# 09_USB_HDMI.net
KiCad netlist of a schematic drawn in Altium Designer
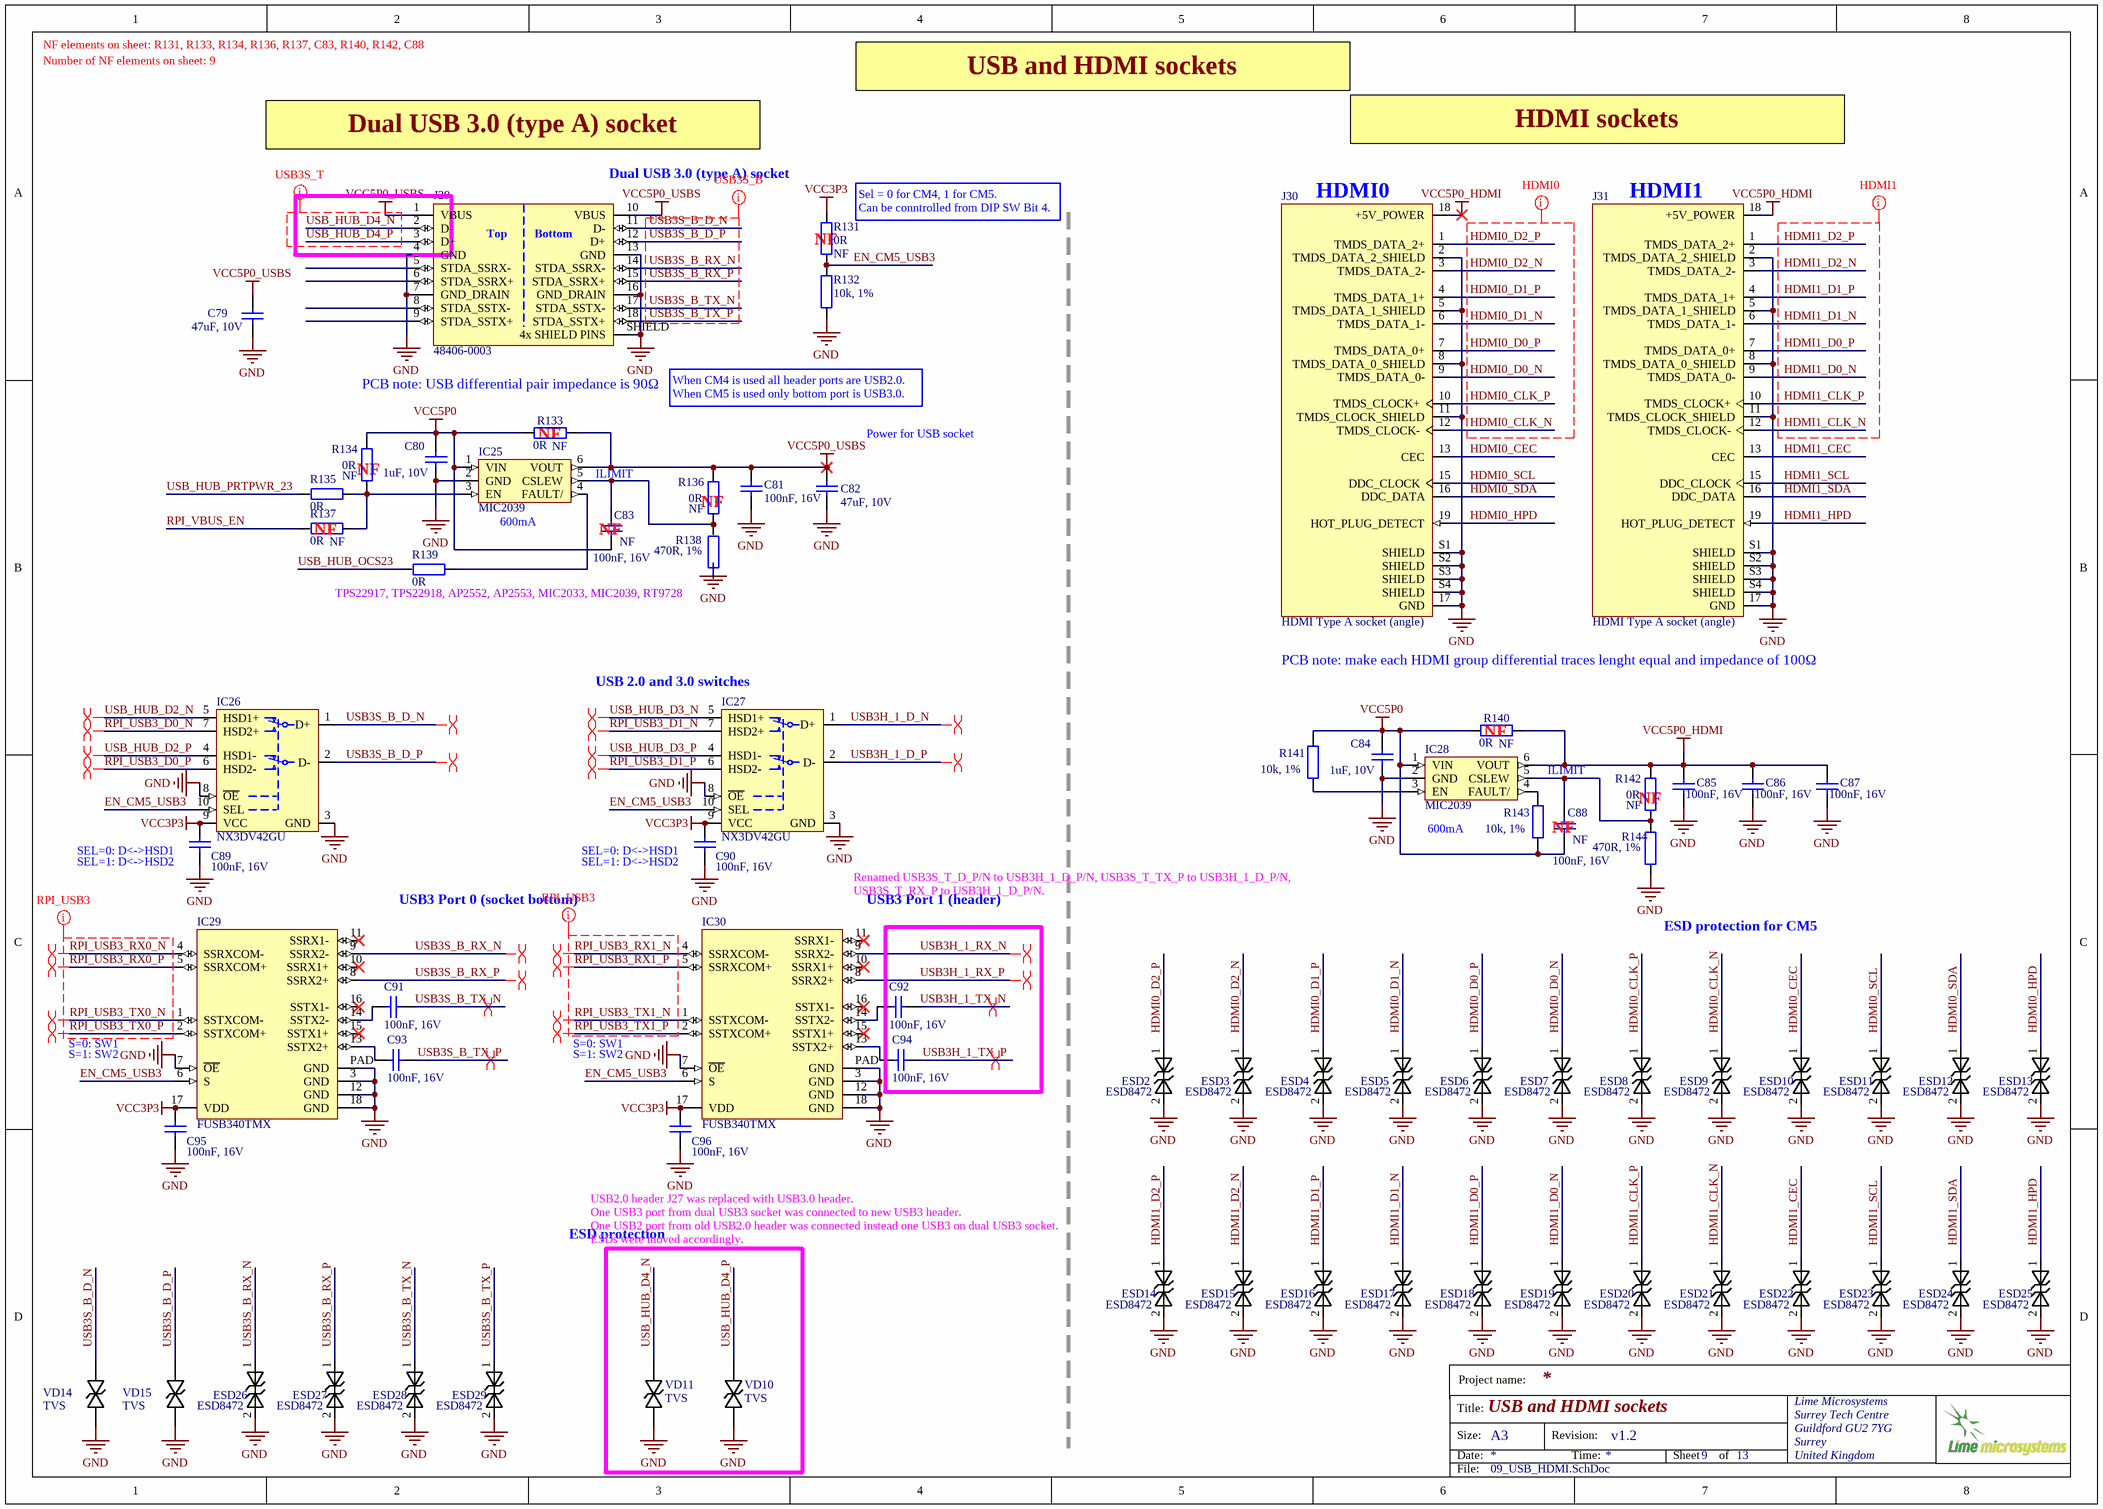
[diagram p0: 09_USB_HDMI.SchDoc]

(export (version "E")
  (design (tool "Eeschema 10.0.6"))
  (components
    (comp (ref "C79")
      (value "47uF, 10V")
      (footprint "CAP1206")
      (fields (field (name "TOLERANCE") "±20%") (field (name "MANUFACTURER") "TDK Corporation"))
      (libsource (lib "LimeFPGAboard_schLib") (part "Cap_1206"))
    )
    (comp (ref "C80")
      (value "1uF, 10V")
      (footprint "CAP0402")
      (fields (field (name "MANUFACTURER") "Yageo"))
      (libsource (lib "LimeMicroAltiumLib_schLib") (part "Cap_0402"))
    )
    (comp (ref "C81")
      (value "100nF, 16V")
      (footprint "CAP0402")
      (fields
        (field (name "MANUFACTURER") "Murata Electronics")
        (field (name "TOLERANCE") "10 %")
        (field (name "MANUFACTURER PART NUMBER") "GRM155R71C104KA88D")
      )
      (libsource (lib "LimeMicroAltiumLib_schLib") (part "Cap_0402"))
    )
    (comp (ref "C82")
      (value "47uF, 10V")
      (footprint "CAP1206")
      (fields (field (name "TOLERANCE") "±20%") (field (name "MANUFACTURER") "TDK Corporation"))
      (libsource (lib "LimeFPGAboard_schLib") (part "Cap_1206"))
    )
    (comp (ref "C83")
      (value "100nF, 16V")
      (footprint "CAP0402")
      (fields
        (field (name "ASSEMBLY INFO") "NF")
        (field (name "MANUFACTURER") "Murata Electronics")
        (field (name "TOLERANCE") "10 %")
        (field (name "MANUFACTURER PART NUMBER") "GRM155R71C104KA88D")
      )
      (libsource (lib "LimeMicroAltiumLib_schLib") (part "Cap_0402"))
    )
    (comp (ref "C84")
      (value "1uF, 10V")
      (footprint "CAP0402")
      (fields (field (name "MANUFACTURER") "Yageo"))
      (libsource (lib "LimeMicroAltiumLib_schLib") (part "Cap_0402"))
    )
    (comp (ref "C85")
      (value "100nF, 16V")
      (footprint "CAP0402")
      (fields
        (field (name "MANUFACTURER") "Murata Electronics")
        (field (name "TOLERANCE") "10 %")
        (field (name "MANUFACTURER PART NUMBER") "GRM155R71C104KA88D")
      )
      (libsource (lib "LimeMicroAltiumLib_schLib") (part "Cap_0402"))
    )
    (comp (ref "C86")
      (value "100nF, 16V")
      (footprint "CAP0402")
      (fields
        (field (name "MANUFACTURER") "Murata Electronics")
        (field (name "TOLERANCE") "10 %")
        (field (name "MANUFACTURER PART NUMBER") "GRM155R71C104KA88D")
      )
      (libsource (lib "LimeMicroAltiumLib_schLib") (part "Cap_0402"))
    )
    (comp (ref "C87")
      (value "100nF, 16V")
      (footprint "CAP0402")
      (fields
        (field (name "MANUFACTURER") "Murata Electronics")
        (field (name "TOLERANCE") "10 %")
        (field (name "MANUFACTURER PART NUMBER") "GRM155R71C104KA88D")
      )
      (libsource (lib "LimeMicroAltiumLib_schLib") (part "Cap_0402"))
    )
    (comp (ref "C88")
      (value "100nF, 16V")
      (footprint "CAP0402")
      (fields
        (field (name "ASSEMBLY INFO") "NF")
        (field (name "MANUFACTURER") "Murata Electronics")
        (field (name "TOLERANCE") "10 %")
        (field (name "MANUFACTURER PART NUMBER") "GRM155R71C104KA88D")
      )
      (libsource (lib "LimeMicroAltiumLib_schLib") (part "Cap_0402"))
    )
    (comp (ref "C89")
      (value "100nF, 16V")
      (footprint "CAP0402")
      (fields
        (field (name "MANUFACTURER") "Murata Electronics")
        (field (name "TOLERANCE") "10 %")
        (field (name "MANUFACTURER PART NUMBER") "GRM155R71C104KA88D")
      )
      (libsource (lib "") (part "Cap_0402_1"))
    )
    (comp (ref "C90")
      (value "100nF, 16V")
      (footprint "CAP0402")
      (fields
        (field (name "MANUFACTURER") "Murata Electronics")
        (field (name "TOLERANCE") "10 %")
        (field (name "MANUFACTURER PART NUMBER") "GRM155R71C104KA88D")
      )
      (libsource (lib "") (part "Cap_0402_1"))
    )
    (comp (ref "C91")
      (value "100nF, 16V")
      (footprint "CAP0402")
      (fields
        (field (name "MANUFACTURER") "Murata Electronics")
        (field (name "TOLERANCE") "10 %")
        (field (name "MANUFACTURER PART NUMBER") "GRM155R71C104KA88D")
      )
      (libsource (lib "") (part "Cap_0402_1"))
    )
    (comp (ref "C92")
      (value "100nF, 16V")
      (footprint "CAP0402")
      (fields
        (field (name "MANUFACTURER") "Murata Electronics")
        (field (name "TOLERANCE") "10 %")
        (field (name "MANUFACTURER PART NUMBER") "GRM155R71C104KA88D")
      )
      (libsource (lib "") (part "Cap_0402_1"))
    )
    (comp (ref "C93")
      (value "100nF, 16V")
      (footprint "CAP0402")
      (fields
        (field (name "MANUFACTURER") "Murata Electronics")
        (field (name "TOLERANCE") "10 %")
        (field (name "MANUFACTURER PART NUMBER") "GRM155R71C104KA88D")
      )
      (libsource (lib "") (part "Cap_0402_1"))
    )
    (comp (ref "C94")
      (value "100nF, 16V")
      (footprint "CAP0402")
      (fields
        (field (name "MANUFACTURER") "Murata Electronics")
        (field (name "TOLERANCE") "10 %")
        (field (name "MANUFACTURER PART NUMBER") "GRM155R71C104KA88D")
      )
      (libsource (lib "") (part "Cap_0402_1"))
    )
    (comp (ref "C95")
      (value "100nF, 16V")
      (footprint "CAP0402")
      (fields
        (field (name "MANUFACTURER") "Murata Electronics")
        (field (name "TOLERANCE") "10 %")
        (field (name "MANUFACTURER PART NUMBER") "GRM155R71C104KA88D")
      )
      (libsource (lib "") (part "Cap_0402_1"))
    )
    (comp (ref "C96")
      (value "100nF, 16V")
      (footprint "CAP0402")
      (fields
        (field (name "MANUFACTURER") "Murata Electronics")
        (field (name "TOLERANCE") "10 %")
        (field (name "MANUFACTURER PART NUMBER") "GRM155R71C104KA88D")
      )
      (libsource (lib "") (part "Cap_0402_1"))
    )
    (comp (ref "ESD2")
      (value "ESD8472")
      (footprint "ESD8472_X3DFN2")
      (fields (field (name "MANUFACTURER") "ON Semiconductor"))
      (libsource (lib "LimeMicroAltiumLib_schLib") (part "ESD8472"))
    )
    (comp (ref "ESD3")
      (value "ESD8472")
      (footprint "ESD8472_X3DFN2")
      (fields (field (name "MANUFACTURER") "ON Semiconductor"))
      (libsource (lib "LimeMicroAltiumLib_schLib") (part "ESD8472"))
    )
    (comp (ref "ESD4")
      (value "ESD8472")
      (footprint "ESD8472_X3DFN2")
      (fields (field (name "MANUFACTURER") "ON Semiconductor"))
      (libsource (lib "LimeMicroAltiumLib_schLib") (part "ESD8472"))
    )
    (comp (ref "ESD5")
      (value "ESD8472")
      (footprint "ESD8472_X3DFN2")
      (fields (field (name "MANUFACTURER") "ON Semiconductor"))
      (libsource (lib "LimeMicroAltiumLib_schLib") (part "ESD8472"))
    )
    (comp (ref "ESD6")
      (value "ESD8472")
      (footprint "ESD8472_X3DFN2")
      (fields (field (name "MANUFACTURER") "ON Semiconductor"))
      (libsource (lib "LimeMicroAltiumLib_schLib") (part "ESD8472"))
    )
    (comp (ref "ESD7")
      (value "ESD8472")
      (footprint "ESD8472_X3DFN2")
      (fields (field (name "MANUFACTURER") "ON Semiconductor"))
      (libsource (lib "LimeMicroAltiumLib_schLib") (part "ESD8472"))
    )
    (comp (ref "ESD8")
      (value "ESD8472")
      (footprint "ESD8472_X3DFN2")
      (fields (field (name "MANUFACTURER") "ON Semiconductor"))
      (libsource (lib "LimeMicroAltiumLib_schLib") (part "ESD8472"))
    )
    (comp (ref "ESD9")
      (value "ESD8472")
      (footprint "ESD8472_X3DFN2")
      (fields (field (name "MANUFACTURER") "ON Semiconductor"))
      (libsource (lib "LimeMicroAltiumLib_schLib") (part "ESD8472"))
    )
    (comp (ref "ESD10")
      (value "ESD8472")
      (footprint "ESD8472_X3DFN2")
      (fields (field (name "MANUFACTURER") "ON Semiconductor"))
      (libsource (lib "LimeMicroAltiumLib_schLib") (part "ESD8472"))
    )
    (comp (ref "ESD11")
      (value "ESD8472")
      (footprint "ESD8472_X3DFN2")
      (fields (field (name "MANUFACTURER") "ON Semiconductor"))
      (libsource (lib "LimeMicroAltiumLib_schLib") (part "ESD8472"))
    )
    (comp (ref "ESD12")
      (value "ESD8472")
      (footprint "ESD8472_X3DFN2")
      (fields (field (name "MANUFACTURER") "ON Semiconductor"))
      (libsource (lib "LimeMicroAltiumLib_schLib") (part "ESD8472"))
    )
    (comp (ref "ESD13")
      (value "ESD8472")
      (footprint "ESD8472_X3DFN2")
      (fields (field (name "MANUFACTURER") "ON Semiconductor"))
      (libsource (lib "LimeMicroAltiumLib_schLib") (part "ESD8472"))
    )
    (comp (ref "ESD14")
      (value "ESD8472")
      (footprint "ESD8472_X3DFN2")
      (fields (field (name "MANUFACTURER") "ON Semiconductor"))
      (libsource (lib "LimeMicroAltiumLib_schLib") (part "ESD8472"))
    )
    (comp (ref "ESD15")
      (value "ESD8472")
      (footprint "ESD8472_X3DFN2")
      (fields (field (name "MANUFACTURER") "ON Semiconductor"))
      (libsource (lib "LimeMicroAltiumLib_schLib") (part "ESD8472"))
    )
    (comp (ref "ESD16")
      (value "ESD8472")
      (footprint "ESD8472_X3DFN2")
      (fields (field (name "MANUFACTURER") "ON Semiconductor"))
      (libsource (lib "LimeMicroAltiumLib_schLib") (part "ESD8472"))
    )
    (comp (ref "ESD17")
      (value "ESD8472")
      (footprint "ESD8472_X3DFN2")
      (fields (field (name "MANUFACTURER") "ON Semiconductor"))
      (libsource (lib "LimeMicroAltiumLib_schLib") (part "ESD8472"))
    )
    (comp (ref "ESD18")
      (value "ESD8472")
      (footprint "ESD8472_X3DFN2")
      (fields (field (name "MANUFACTURER") "ON Semiconductor"))
      (libsource (lib "LimeMicroAltiumLib_schLib") (part "ESD8472"))
    )
    (comp (ref "ESD19")
      (value "ESD8472")
      (footprint "ESD8472_X3DFN2")
      (fields (field (name "MANUFACTURER") "ON Semiconductor"))
      (libsource (lib "LimeMicroAltiumLib_schLib") (part "ESD8472"))
    )
    (comp (ref "ESD20")
      (value "ESD8472")
      (footprint "ESD8472_X3DFN2")
      (fields (field (name "MANUFACTURER") "ON Semiconductor"))
      (libsource (lib "LimeMicroAltiumLib_schLib") (part "ESD8472"))
    )
    (comp (ref "ESD21")
      (value "ESD8472")
      (footprint "ESD8472_X3DFN2")
      (fields (field (name "MANUFACTURER") "ON Semiconductor"))
      (libsource (lib "LimeMicroAltiumLib_schLib") (part "ESD8472"))
    )
    (comp (ref "ESD22")
      (value "ESD8472")
      (footprint "ESD8472_X3DFN2")
      (fields (field (name "MANUFACTURER") "ON Semiconductor"))
      (libsource (lib "LimeMicroAltiumLib_schLib") (part "ESD8472"))
    )
    (comp (ref "ESD23")
      (value "ESD8472")
      (footprint "ESD8472_X3DFN2")
      (fields (field (name "MANUFACTURER") "ON Semiconductor"))
      (libsource (lib "LimeMicroAltiumLib_schLib") (part "ESD8472"))
    )
    (comp (ref "ESD24")
      (value "ESD8472")
      (footprint "ESD8472_X3DFN2")
      (fields (field (name "MANUFACTURER") "ON Semiconductor"))
      (libsource (lib "LimeMicroAltiumLib_schLib") (part "ESD8472"))
    )
    (comp (ref "ESD25")
      (value "ESD8472")
      (footprint "ESD8472_X3DFN2")
      (fields (field (name "MANUFACTURER") "ON Semiconductor"))
      (libsource (lib "LimeMicroAltiumLib_schLib") (part "ESD8472"))
    )
    (comp (ref "ESD26")
      (value "ESD8472")
      (footprint "ESD8472_X3DFN2")
      (fields (field (name "MANUFACTURER") "ON Semiconductor"))
      (libsource (lib "LimeMicroAltiumLib_schLib") (part "ESD8472"))
    )
    (comp (ref "ESD27")
      (value "ESD8472")
      (footprint "ESD8472_X3DFN2")
      (fields (field (name "MANUFACTURER") "ON Semiconductor"))
      (libsource (lib "LimeMicroAltiumLib_schLib") (part "ESD8472"))
    )
    (comp (ref "ESD28")
      (value "ESD8472")
      (footprint "ESD8472_X3DFN2")
      (fields (field (name "MANUFACTURER") "ON Semiconductor"))
      (libsource (lib "LimeMicroAltiumLib_schLib") (part "ESD8472"))
    )
    (comp (ref "ESD29")
      (value "ESD8472")
      (footprint "ESD8472_X3DFN2")
      (fields (field (name "MANUFACTURER") "ON Semiconductor"))
      (libsource (lib "LimeMicroAltiumLib_schLib") (part "ESD8472"))
    )
    (comp (ref "IC25")
      (value "MIC2039")
      (footprint "SOT23-6")
      (fields (field (name "MANUFACTURER") "Microchip"))
      (libsource (lib "LimeMicroAltiumLib_schLib_r04") (part "MIC2033_power_switch"))
    )
    (comp (ref "IC26")
      (value "NX3DV42GU")
      (footprint "FSUSB42UMX")
      (fields (field (name "MANUFACTURER") "NXP Semiconductors"))
      (libsource (lib "LimeMicroAltiumLib_schLib_r01") (part "FSUSB42UMX"))
    )
    (comp (ref "IC27")
      (value "NX3DV42GU")
      (footprint "FSUSB42UMX")
      (fields (field (name "MANUFACTURER") "NXP Semiconductors"))
      (libsource (lib "LimeMicroAltiumLib_schLib_r01") (part "FSUSB42UMX"))
    )
    (comp (ref "IC28")
      (value "MIC2039")
      (footprint "SOT23-6")
      (fields (field (name "MANUFACTURER") "Microchip"))
      (libsource (lib "LimeMicroAltiumLib_schLib_r04") (part "MIC2033_power_switch"))
    )
    (comp (ref "IC29")
      (value "FUSB340TMX")
      (footprint "FUSB340TMX_USB_switch_18-XFQFN")
      (fields (field (name "MANUFACTURER") "ON Semiconductor / Fairchild"))
      (libsource (lib "LimeMicroAltiumLib") (part "FUSB340TMX_USB_switch"))
    )
    (comp (ref "IC30")
      (value "FUSB340TMX")
      (footprint "FUSB340TMX_USB_switch_18-XFQFN")
      (fields (field (name "MANUFACTURER") "ON Semiconductor / Fairchild"))
      (libsource (lib "LimeMicroAltiumLib") (part "FUSB340TMX_USB_switch"))
    )
    (comp (ref "J29")
      (value "48406-0003")
      (footprint "Dual_USB_48406-0003_Molex")
      (fields (field (name "MANUFACTURER") "Molex"))
      (libsource (lib "LimeMicroAltiumLib") (part "Dual_USB_48406-0003_Molex"))
    )
    (comp (ref "J30")
      (value "HDMI Type A socket (angle)")
      (footprint "HDMI_HD01-19-RA-TH")
      (fields (field (name "MANUFACTURER") "CUI Devices"))
      (libsource (lib "LimeMicroAltiumLib_schLib_r04") (part "HDMI_HD01-19-RA-TH"))
    )
    (comp (ref "J31")
      (value "HDMI Type A socket (angle)")
      (footprint "HDMI_HD01-19-RA-TH")
      (fields (field (name "MANUFACTURER") "CUI Devices"))
      (libsource (lib "LimeMicroAltiumLib_schLib_r04") (part "HDMI_HD01-19-RA-TH"))
    )
    (comp (ref "R131")
      (value "0R")
      (footprint "RES0402")
      (fields
        (field (name "ASSEMBLY INFO") "NF")
        (field (name "MANUFACTURER") "Yageo")
        (field (name "TOLERANCE") "Jumper")
      )
      (libsource (lib "") (part "Res_0402_1"))
    )
    (comp (ref "R132")
      (value "10k, 1%")
      (footprint "RES0402")
      (fields (field (name "MANUFACTURER") "Yageo") (field (name "TOLERANCE") "±1%"))
      (libsource (lib "") (part "Res_0402_1"))
    )
    (comp (ref "R133")
      (value "0R")
      (footprint "RES0402")
      (fields
        (field (name "ASSEMBLY INFO") "NF")
        (field (name "MANUFACTURER") "Yageo")
        (field (name "TOLERANCE") "Jumper")
      )
      (libsource (lib "LimeMicroAltiumLib_schLib") (part "Res_0402"))
    )
    (comp (ref "R134")
      (value "0R")
      (footprint "RES0402")
      (fields
        (field (name "ASSEMBLY INFO") "NF")
        (field (name "MANUFACTURER") "Yageo")
        (field (name "TOLERANCE") "Jumper")
      )
      (libsource (lib "LimeMicroAltiumLib_schLib") (part "Res_0402"))
    )
    (comp (ref "R135")
      (value "0R")
      (footprint "RES0402")
      (fields (field (name "MANUFACTURER") "Yageo") (field (name "TOLERANCE") "Jumper"))
      (libsource (lib "LimeMicroAltiumLib_schLib") (part "Res_0402"))
    )
    (comp (ref "R136")
      (value "0R")
      (footprint "RES0402")
      (fields
        (field (name "ASSEMBLY INFO") "NF")
        (field (name "MANUFACTURER") "Yageo")
        (field (name "TOLERANCE") "Jumper")
      )
      (libsource (lib "LimeMicroAltiumLib_schLib") (part "Res_0402"))
    )
    (comp (ref "R137")
      (value "0R")
      (footprint "RES0402")
      (fields
        (field (name "ASSEMBLY INFO") "NF")
        (field (name "MANUFACTURER") "Yageo")
        (field (name "TOLERANCE") "Jumper")
      )
      (libsource (lib "LimeMicroAltiumLib_schLib") (part "Res_0402"))
    )
    (comp (ref "R138")
      (value "470R, 1%")
      (footprint "RES0402")
      (fields (field (name "TOLERANCE") "1%") (field (name "MANUFACTURER") "Yageo"))
      (libsource (lib "LimeMicroAltiumLib_schLib") (part "Res_0402"))
    )
    (comp (ref "R139")
      (value "0R")
      (footprint "RES0402")
      (fields (field (name "MANUFACTURER") "Yageo") (field (name "TOLERANCE") "Jumper"))
      (libsource (lib "LimeMicroAltiumLib_schLib") (part "Res_0402"))
    )
    (comp (ref "R140")
      (value "0R")
      (footprint "RES0402")
      (fields
        (field (name "ASSEMBLY INFO") "NF")
        (field (name "MANUFACTURER") "Yageo")
        (field (name "TOLERANCE") "Jumper")
      )
      (libsource (lib "LimeMicroAltiumLib_schLib") (part "Res_0402"))
    )
    (comp (ref "R141")
      (value "10k, 1%")
      (footprint "RES0402")
      (fields (field (name "MANUFACTURER") "Yageo") (field (name "TOLERANCE") "±1%"))
      (libsource (lib "") (part "Res_0402_1"))
    )
    (comp (ref "R142")
      (value "0R")
      (footprint "RES0402")
      (fields
        (field (name "ASSEMBLY INFO") "NF")
        (field (name "MANUFACTURER") "Yageo")
        (field (name "TOLERANCE") "Jumper")
      )
      (libsource (lib "LimeMicroAltiumLib_schLib") (part "Res_0402"))
    )
    (comp (ref "R143")
      (value "10k, 1%")
      (footprint "RES0402")
      (fields (field (name "MANUFACTURER") "Yageo") (field (name "TOLERANCE") "±1%"))
      (libsource (lib "") (part "Res_0402_1"))
    )
    (comp (ref "R144")
      (value "470R, 1%")
      (footprint "RES0402")
      (fields (field (name "TOLERANCE") "1%") (field (name "MANUFACTURER") "Yageo"))
      (libsource (lib "LimeMicroAltiumLib_schLib") (part "Res_0402"))
    )
    (comp (ref "VD10")
      (value "TVS")
      (footprint "SOD323")
      (fields
        (field (name "MANUFACTURER PART NUMBER") "SD03LCC")
        (field (name "MANUFACTURER") "Sangdest Microelectronics")
      )
      (libsource (lib "LimeNet-Micro_2v1-SDR") (part "DIODE_TVS"))
    )
    (comp (ref "VD11")
      (value "TVS")
      (footprint "SOD323")
      (fields
        (field (name "MANUFACTURER PART NUMBER") "SD03LCC")
        (field (name "MANUFACTURER") "Sangdest Microelectronics")
      )
      (libsource (lib "LimeNet-Micro_2v1-SDR") (part "DIODE_TVS"))
    )
    (comp (ref "VD14")
      (value "TVS")
      (footprint "SOD323")
      (fields
        (field (name "MANUFACTURER PART NUMBER") "SD03LCC")
        (field (name "MANUFACTURER") "Sangdest Microelectronics")
      )
      (libsource (lib "LimeNet-Micro_2v1-SDR") (part "DIODE_TVS"))
    )
    (comp (ref "VD15")
      (value "TVS")
      (footprint "SOD323")
      (fields
        (field (name "MANUFACTURER PART NUMBER") "SD03LCC")
        (field (name "MANUFACTURER") "Sangdest Microelectronics")
      )
      (libsource (lib "LimeNet-Micro_2v1-SDR") (part "DIODE_TVS"))
    )
  )
  (nets
    (net (code "1") (name "/EN_CM5_USB3") (class "Default")
      (node (ref "IC26") (pin "10") (pinfunction "SEL_10") (pintype "input"))
      (node (ref "IC27") (pin "10") (pinfunction "SEL_10") (pintype "input"))
      (node (ref "IC29") (pin "6") (pinfunction "S_6") (pintype "input"))
      (node (ref "IC30") (pin "6") (pinfunction "S_6") (pintype "input"))
      (node (ref "R131") (pin "1") (pinfunction "1_1") (pintype "passive"))
      (node (ref "R132") (pin "1") (pinfunction "1_1") (pintype "passive"))
    )
    (net (code "2") (name "/HDMI0_CEC") (class "Default")
      (node (ref "ESD10") (pin "1") (pinfunction "1_1") (pintype "passive"))
      (node (ref "J30") (pin "13") (pinfunction "CEC_13") (pintype "bidirectional"))
    )
    (net (code "3") (name "/HDMI0_CLK_N") (class "Default")
      (node (ref "ESD9") (pin "1") (pinfunction "1_1") (pintype "passive"))
      (node (ref "J30") (pin "12") (pinfunction "TMDS_CLOCK-_12") (pintype "bidirectional"))
    )
    (net (code "4") (name "/HDMI0_CLK_P") (class "Default")
      (node (ref "ESD8") (pin "1") (pinfunction "1_1") (pintype "passive"))
      (node (ref "J30") (pin "10") (pinfunction "TMDS_CLOCK+_10") (pintype "bidirectional"))
    )
    (net (code "5") (name "/HDMI0_D0_N") (class "Default")
      (node (ref "ESD7") (pin "1") (pinfunction "1_1") (pintype "passive"))
      (node (ref "J30") (pin "9") (pinfunction "TMDS_DATA_0-_9") (pintype "bidirectional"))
    )
    (net (code "6") (name "/HDMI0_D0_P") (class "Default")
      (node (ref "ESD6") (pin "1") (pinfunction "1_1") (pintype "passive"))
      (node (ref "J30") (pin "7") (pinfunction "TMDS_DATA_0+_7") (pintype "bidirectional"))
    )
    (net (code "7") (name "/HDMI0_D1_N") (class "Default")
      (node (ref "ESD5") (pin "1") (pinfunction "1_1") (pintype "passive"))
      (node (ref "J30") (pin "6") (pinfunction "TMDS_DATA_1-_6") (pintype "bidirectional"))
    )
    (net (code "8") (name "/HDMI0_D1_P") (class "Default")
      (node (ref "ESD4") (pin "1") (pinfunction "1_1") (pintype "passive"))
      (node (ref "J30") (pin "4") (pinfunction "TMDS_DATA_1+_4") (pintype "bidirectional"))
    )
    (net (code "9") (name "/HDMI0_D2_N") (class "Default")
      (node (ref "ESD3") (pin "1") (pinfunction "1_1") (pintype "passive"))
      (node (ref "J30") (pin "3") (pinfunction "TMDS_DATA_2-_3") (pintype "bidirectional"))
    )
    (net (code "10") (name "/HDMI0_D2_P") (class "Default")
      (node (ref "ESD2") (pin "1") (pinfunction "1_1") (pintype "passive"))
      (node (ref "J30") (pin "1") (pinfunction "TMDS_DATA_2+_1") (pintype "bidirectional"))
    )
    (net (code "11") (name "/HDMI0_HPD") (class "Default")
      (node (ref "ESD13") (pin "1") (pinfunction "1_1") (pintype "passive"))
      (node (ref "J30") (pin "19") (pinfunction "HOT_PLUG_DETECT_19") (pintype "input"))
    )
    (net (code "12") (name "/HDMI0_SCL") (class "Default")
      (node (ref "ESD11") (pin "1") (pinfunction "1_1") (pintype "passive"))
      (node (ref "J30") (pin "15") (pinfunction "DDC_CLOCK_15") (pintype "bidirectional"))
    )
    (net (code "13") (name "/HDMI0_SDA") (class "Default")
      (node (ref "ESD12") (pin "1") (pinfunction "1_1") (pintype "passive"))
      (node (ref "J30") (pin "16") (pinfunction "DDC_DATA_16") (pintype "bidirectional"))
    )
    (net (code "14") (name "/HDMI1_CEC") (class "Default")
      (node (ref "ESD22") (pin "1") (pinfunction "1_1") (pintype "passive"))
      (node (ref "J31") (pin "13") (pinfunction "CEC_13") (pintype "bidirectional"))
    )
    (net (code "15") (name "/HDMI1_CLK_N") (class "Default")
      (node (ref "ESD21") (pin "1") (pinfunction "1_1") (pintype "passive"))
      (node (ref "J31") (pin "12") (pinfunction "TMDS_CLOCK-_12") (pintype "bidirectional"))
    )
    (net (code "16") (name "/HDMI1_CLK_P") (class "Default")
      (node (ref "ESD20") (pin "1") (pinfunction "1_1") (pintype "passive"))
      (node (ref "J31") (pin "10") (pinfunction "TMDS_CLOCK+_10") (pintype "bidirectional"))
    )
    (net (code "17") (name "/HDMI1_D0_N") (class "Default")
      (node (ref "ESD19") (pin "1") (pinfunction "1_1") (pintype "passive"))
      (node (ref "J31") (pin "9") (pinfunction "TMDS_DATA_0-_9") (pintype "bidirectional"))
    )
    (net (code "18") (name "/HDMI1_D0_P") (class "Default")
      (node (ref "ESD18") (pin "1") (pinfunction "1_1") (pintype "passive"))
      (node (ref "J31") (pin "7") (pinfunction "TMDS_DATA_0+_7") (pintype "bidirectional"))
    )
    (net (code "19") (name "/HDMI1_D1_N") (class "Default")
      (node (ref "ESD17") (pin "1") (pinfunction "1_1") (pintype "passive"))
      (node (ref "J31") (pin "6") (pinfunction "TMDS_DATA_1-_6") (pintype "bidirectional"))
    )
    (net (code "20") (name "/HDMI1_D1_P") (class "Default")
      (node (ref "ESD16") (pin "1") (pinfunction "1_1") (pintype "passive"))
      (node (ref "J31") (pin "4") (pinfunction "TMDS_DATA_1+_4") (pintype "bidirectional"))
    )
    (net (code "21") (name "/HDMI1_D2_N") (class "Default")
      (node (ref "ESD15") (pin "1") (pinfunction "1_1") (pintype "passive"))
      (node (ref "J31") (pin "3") (pinfunction "TMDS_DATA_2-_3") (pintype "bidirectional"))
    )
    (net (code "22") (name "/HDMI1_D2_P") (class "Default")
      (node (ref "ESD14") (pin "1") (pinfunction "1_1") (pintype "passive"))
      (node (ref "J31") (pin "1") (pinfunction "TMDS_DATA_2+_1") (pintype "bidirectional"))
    )
    (net (code "23") (name "/HDMI1_HPD") (class "Default")
      (node (ref "ESD25") (pin "1") (pinfunction "1_1") (pintype "passive"))
      (node (ref "J31") (pin "19") (pinfunction "HOT_PLUG_DETECT_19") (pintype "input"))
    )
    (net (code "24") (name "/HDMI1_SCL") (class "Default")
      (node (ref "ESD23") (pin "1") (pinfunction "1_1") (pintype "passive"))
      (node (ref "J31") (pin "15") (pinfunction "DDC_CLOCK_15") (pintype "bidirectional"))
    )
    (net (code "25") (name "/HDMI1_SDA") (class "Default")
      (node (ref "ESD24") (pin "1") (pinfunction "1_1") (pintype "passive"))
      (node (ref "J31") (pin "16") (pinfunction "DDC_DATA_16") (pintype "bidirectional"))
    )
    (net (code "26") (name "/RPI_USB3_D0_N") (class "Default")
      (node (ref "IC26") (pin "7") (pinfunction "HSD2+_7") (pintype "passive"))
    )
    (net (code "27") (name "/RPI_USB3_D0_P") (class "Default")
      (node (ref "IC26") (pin "6") (pinfunction "HSD2-_6") (pintype "passive"))
    )
    (net (code "28") (name "/RPI_USB3_D1_N") (class "Default")
      (node (ref "IC27") (pin "7") (pinfunction "HSD2+_7") (pintype "passive"))
    )
    (net (code "29") (name "/RPI_USB3_D1_P") (class "Default")
      (node (ref "IC27") (pin "6") (pinfunction "HSD2-_6") (pintype "passive"))
    )
    (net (code "30") (name "/RPI_USB3_RX0_N") (class "Default")
      (node (ref "IC29") (pin "4") (pinfunction "SSRXCOM-_4") (pintype "bidirectional"))
    )
    (net (code "31") (name "/RPI_USB3_RX0_P") (class "Default")
      (node (ref "IC29") (pin "5") (pinfunction "SSRXCOM+_5") (pintype "bidirectional"))
    )
    (net (code "32") (name "/RPI_USB3_RX1_N") (class "Default")
      (node (ref "IC30") (pin "4") (pinfunction "SSRXCOM-_4") (pintype "bidirectional"))
    )
    (net (code "33") (name "/RPI_USB3_RX1_P") (class "Default")
      (node (ref "IC30") (pin "5") (pinfunction "SSRXCOM+_5") (pintype "bidirectional"))
    )
    (net (code "34") (name "/RPI_USB3_TX0_N") (class "Default")
      (node (ref "IC29") (pin "1") (pinfunction "SSTXCOM-_1") (pintype "bidirectional"))
    )
    (net (code "35") (name "/RPI_USB3_TX0_P") (class "Default")
      (node (ref "IC29") (pin "2") (pinfunction "SSTXCOM+_2") (pintype "bidirectional"))
    )
    (net (code "36") (name "/RPI_USB3_TX1_N") (class "Default")
      (node (ref "IC30") (pin "1") (pinfunction "SSTXCOM-_1") (pintype "bidirectional"))
    )
    (net (code "37") (name "/RPI_USB3_TX1_P") (class "Default")
      (node (ref "IC30") (pin "2") (pinfunction "SSTXCOM+_2") (pintype "bidirectional"))
    )
    (net (code "38") (name "/RPI_VBUS_EN") (class "Default")
      (node (ref "R137") (pin "2") (pinfunction "2_2") (pintype "passive"))
    )
    (net (code "39") (name "/USB3H_1_D_N") (class "Default")
      (node (ref "IC27") (pin "1") (pinfunction "D+_1") (pintype "passive"))
    )
    (net (code "40") (name "/USB3H_1_D_P") (class "Default")
      (node (ref "IC27") (pin "2") (pinfunction "D-_2") (pintype "passive"))
    )
    (net (code "41") (name "/USB3H_1_RX_N") (class "Default")
      (node (ref "IC30") (pin "9") (pinfunction "SSRX2-_9") (pintype "bidirectional"))
    )
    (net (code "42") (name "/USB3H_1_RX_P") (class "Default")
      (node (ref "IC30") (pin "8") (pinfunction "SSRX2+_8") (pintype "bidirectional"))
    )
    (net (code "43") (name "/USB3H_1_TX_N") (class "Default")
      (node (ref "C92") (pin "2") (pinfunction "2_2") (pintype "passive"))
    )
    (net (code "44") (name "/USB3H_1_TX_P") (class "Default")
      (node (ref "C94") (pin "2") (pinfunction "2_2") (pintype "passive"))
    )
    (net (code "45") (name "/USB3S_B_D_N") (class "Default")
      (node (ref "IC26") (pin "1") (pinfunction "D+_1") (pintype "passive"))
      (node (ref "J29") (pin "11") (pinfunction "D-_11") (pintype "bidirectional"))
      (node (ref "VD14") (pin "A") (pinfunction "A_A") (pintype "passive"))
    )
    (net (code "46") (name "/USB3S_B_D_P") (class "Default")
      (node (ref "IC26") (pin "2") (pinfunction "D-_2") (pintype "passive"))
      (node (ref "J29") (pin "12") (pinfunction "D+_12") (pintype "bidirectional"))
      (node (ref "VD15") (pin "A") (pinfunction "A_A") (pintype "passive"))
    )
    (net (code "47") (name "/USB3S_B_RX_N") (class "Default")
      (node (ref "ESD26") (pin "1") (pinfunction "1_1") (pintype "passive"))
      (node (ref "IC29") (pin "9") (pinfunction "SSRX2-_9") (pintype "bidirectional"))
      (node (ref "J29") (pin "14") (pinfunction "STDA_SSRX-_14") (pintype "bidirectional"))
    )
    (net (code "48") (name "/USB3S_B_RX_P") (class "Default")
      (node (ref "ESD27") (pin "1") (pinfunction "1_1") (pintype "passive"))
      (node (ref "IC29") (pin "8") (pinfunction "SSRX2+_8") (pintype "bidirectional"))
      (node (ref "J29") (pin "15") (pinfunction "STDA_SSRX+_15") (pintype "bidirectional"))
    )
    (net (code "49") (name "/USB3S_B_TX_N") (class "Default")
      (node (ref "C91") (pin "2") (pinfunction "2_2") (pintype "passive"))
      (node (ref "ESD28") (pin "1") (pinfunction "1_1") (pintype "passive"))
      (node (ref "J29") (pin "17") (pinfunction "STDA_SSTX-_17") (pintype "bidirectional"))
    )
    (net (code "50") (name "/USB3S_B_TX_P") (class "Default")
      (node (ref "C93") (pin "2") (pinfunction "2_2") (pintype "passive"))
      (node (ref "ESD29") (pin "1") (pinfunction "1_1") (pintype "passive"))
      (node (ref "J29") (pin "18") (pinfunction "STDA_SSTX+_18") (pintype "bidirectional"))
    )
    (net (code "51") (name "/USB_HUB_D2_N") (class "Default")
      (node (ref "IC26") (pin "5") (pinfunction "HSD1+_5") (pintype "passive"))
    )
    (net (code "52") (name "/USB_HUB_D2_P") (class "Default")
      (node (ref "IC26") (pin "4") (pinfunction "HSD1-_4") (pintype "passive"))
    )
    (net (code "53") (name "/USB_HUB_D3_N") (class "Default")
      (node (ref "IC27") (pin "5") (pinfunction "HSD1+_5") (pintype "passive"))
    )
    (net (code "54") (name "/USB_HUB_D3_P") (class "Default")
      (node (ref "IC27") (pin "4") (pinfunction "HSD1-_4") (pintype "passive"))
    )
    (net (code "55") (name "/USB_HUB_D4_N") (class "Default")
      (node (ref "J29") (pin "2") (pinfunction "D-_2") (pintype "bidirectional"))
      (node (ref "VD11") (pin "A") (pinfunction "A_A") (pintype "passive"))
    )
    (net (code "56") (name "/USB_HUB_D4_P") (class "Default")
      (node (ref "J29") (pin "3") (pinfunction "D+_3") (pintype "bidirectional"))
      (node (ref "VD10") (pin "A") (pinfunction "A_A") (pintype "passive"))
    )
    (net (code "57") (name "/USB_HUB_OCS23") (class "Default")
      (node (ref "R139") (pin "2") (pinfunction "2_2") (pintype "passive"))
    )
    (net (code "58") (name "/USB_HUB_PRTPWR_23") (class "Default")
      (node (ref "R135") (pin "2") (pinfunction "2_2") (pintype "passive"))
    )
    (net (code "59") (name "GND") (class "Default")
      (node (ref "C79") (pin "1") (pinfunction "1_1") (pintype "passive"))
      (node (ref "C80") (pin "2") (pinfunction "2_2") (pintype "passive"))
      (node (ref "C81") (pin "2") (pinfunction "2_2") (pintype "passive"))
      (node (ref "C82") (pin "1") (pinfunction "1_1") (pintype "passive"))
      (node (ref "C84") (pin "2") (pinfunction "2_2") (pintype "passive"))
      (node (ref "C85") (pin "2") (pinfunction "2_2") (pintype "passive"))
      (node (ref "C86") (pin "2") (pinfunction "2_2") (pintype "passive"))
      (node (ref "C87") (pin "2") (pinfunction "2_2") (pintype "passive"))
      (node (ref "C89") (pin "2") (pinfunction "2_2") (pintype "passive"))
      (node (ref "C90") (pin "2") (pinfunction "2_2") (pintype "passive"))
      (node (ref "C95") (pin "2") (pinfunction "2_2") (pintype "passive"))
      (node (ref "C96") (pin "2") (pinfunction "2_2") (pintype "passive"))
      (node (ref "ESD10") (pin "2") (pinfunction "2_2") (pintype "passive"))
      (node (ref "ESD11") (pin "2") (pinfunction "2_2") (pintype "passive"))
      (node (ref "ESD12") (pin "2") (pinfunction "2_2") (pintype "passive"))
      (node (ref "ESD13") (pin "2") (pinfunction "2_2") (pintype "passive"))
      (node (ref "ESD14") (pin "2") (pinfunction "2_2") (pintype "passive"))
      (node (ref "ESD15") (pin "2") (pinfunction "2_2") (pintype "passive"))
      (node (ref "ESD16") (pin "2") (pinfunction "2_2") (pintype "passive"))
      (node (ref "ESD17") (pin "2") (pinfunction "2_2") (pintype "passive"))
      (node (ref "ESD18") (pin "2") (pinfunction "2_2") (pintype "passive"))
      (node (ref "ESD19") (pin "2") (pinfunction "2_2") (pintype "passive"))
      (node (ref "ESD2") (pin "2") (pinfunction "2_2") (pintype "passive"))
      (node (ref "ESD20") (pin "2") (pinfunction "2_2") (pintype "passive"))
      (node (ref "ESD21") (pin "2") (pinfunction "2_2") (pintype "passive"))
      (node (ref "ESD22") (pin "2") (pinfunction "2_2") (pintype "passive"))
      (node (ref "ESD23") (pin "2") (pinfunction "2_2") (pintype "passive"))
      (node (ref "ESD24") (pin "2") (pinfunction "2_2") (pintype "passive"))
      (node (ref "ESD25") (pin "2") (pinfunction "2_2") (pintype "passive"))
      (node (ref "ESD26") (pin "2") (pinfunction "2_2") (pintype "passive"))
      (node (ref "ESD27") (pin "2") (pinfunction "2_2") (pintype "passive"))
      (node (ref "ESD28") (pin "2") (pinfunction "2_2") (pintype "passive"))
      (node (ref "ESD29") (pin "2") (pinfunction "2_2") (pintype "passive"))
      (node (ref "ESD3") (pin "2") (pinfunction "2_2") (pintype "passive"))
      (node (ref "ESD4") (pin "2") (pinfunction "2_2") (pintype "passive"))
      (node (ref "ESD5") (pin "2") (pinfunction "2_2") (pintype "passive"))
      (node (ref "ESD6") (pin "2") (pinfunction "2_2") (pintype "passive"))
      (node (ref "ESD7") (pin "2") (pinfunction "2_2") (pintype "passive"))
      (node (ref "ESD8") (pin "2") (pinfunction "2_2") (pintype "passive"))
      (node (ref "ESD9") (pin "2") (pinfunction "2_2") (pintype "passive"))
      (node (ref "IC25") (pin "2") (pinfunction "GND_2") (pintype "passive"))
      (node (ref "IC26") (pin "3") (pinfunction "GND_3") (pintype "passive"))
      (node (ref "IC26") (pin "8") (pinfunction "~{OE}_8") (pintype "input"))
      (node (ref "IC27") (pin "3") (pinfunction "GND_3") (pintype "passive"))
      (node (ref "IC27") (pin "8") (pinfunction "~{OE}_8") (pintype "input"))
      (node (ref "IC28") (pin "2") (pinfunction "GND_2") (pintype "passive"))
      (node (ref "IC29") (pin "12") (pinfunction "GND_12") (pintype "passive"))
      (node (ref "IC29") (pin "18") (pinfunction "GND_18") (pintype "passive"))
      (node (ref "IC29") (pin "3") (pinfunction "GND_3") (pintype "passive"))
      (node (ref "IC29") (pin "7") (pinfunction "~{OE}_7") (pintype "input"))
      (node (ref "IC29") (pin "PAD") (pinfunction "GND_PAD") (pintype "passive"))
      (node (ref "IC30") (pin "12") (pinfunction "GND_12") (pintype "passive"))
      (node (ref "IC30") (pin "18") (pinfunction "GND_18") (pintype "passive"))
      (node (ref "IC30") (pin "3") (pinfunction "GND_3") (pintype "passive"))
      (node (ref "IC30") (pin "7") (pinfunction "~{OE}_7") (pintype "input"))
      (node (ref "IC30") (pin "PAD") (pinfunction "GND_PAD") (pintype "passive"))
      (node (ref "J29") (pin "13") (pinfunction "GND_13") (pintype "passive"))
      (node (ref "J29") (pin "16") (pinfunction "GND_DRAIN_16") (pintype "passive"))
      (node (ref "J29") (pin "4") (pinfunction "GND_4") (pintype "passive"))
      (node (ref "J29") (pin "7") (pinfunction "GND_DRAIN_7") (pintype "passive"))
      (node (ref "J29") (pin "SHIELD") (pinfunction "4x_SHIELD_PINS_SHIELD") (pintype "passive"))
      (node (ref "J30") (pin "11") (pinfunction "TMDS_CLOCK_SHIELD_11") (pintype "passive"))
      (node (ref "J30") (pin "17") (pinfunction "GND_17") (pintype "power_in"))
      (node (ref "J30") (pin "2") (pinfunction "TMDS_DATA_2_SHIELD_2") (pintype "passive"))
      (node (ref "J30") (pin "5") (pinfunction "TMDS_DATA_1_SHIELD_5") (pintype "passive"))
      (node (ref "J30") (pin "8") (pinfunction "TMDS_DATA_0_SHIELD_8") (pintype "passive"))
      (node (ref "J30") (pin "S1") (pinfunction "SHIELD_S1") (pintype "passive"))
      (node (ref "J30") (pin "S2") (pinfunction "SHIELD_S2") (pintype "passive"))
      (node (ref "J30") (pin "S3") (pinfunction "SHIELD_S3") (pintype "passive"))
      (node (ref "J30") (pin "S4") (pinfunction "SHIELD_S4") (pintype "passive"))
      (node (ref "J31") (pin "11") (pinfunction "TMDS_CLOCK_SHIELD_11") (pintype "passive"))
      (node (ref "J31") (pin "17") (pinfunction "GND_17") (pintype "power_in"))
      (node (ref "J31") (pin "2") (pinfunction "TMDS_DATA_2_SHIELD_2") (pintype "passive"))
      (node (ref "J31") (pin "5") (pinfunction "TMDS_DATA_1_SHIELD_5") (pintype "passive"))
      (node (ref "J31") (pin "8") (pinfunction "TMDS_DATA_0_SHIELD_8") (pintype "passive"))
      (node (ref "J31") (pin "S1") (pinfunction "SHIELD_S1") (pintype "passive"))
      (node (ref "J31") (pin "S2") (pinfunction "SHIELD_S2") (pintype "passive"))
      (node (ref "J31") (pin "S3") (pinfunction "SHIELD_S3") (pintype "passive"))
      (node (ref "J31") (pin "S4") (pinfunction "SHIELD_S4") (pintype "passive"))
      (node (ref "R132") (pin "2") (pinfunction "2_2") (pintype "passive"))
      (node (ref "R138") (pin "1") (pinfunction "1_1") (pintype "passive"))
      (node (ref "R144") (pin "1") (pinfunction "1_1") (pintype "passive"))
      (node (ref "VD10") (pin "K") (pinfunction "K_K") (pintype "passive"))
      (node (ref "VD11") (pin "K") (pinfunction "K_K") (pintype "passive"))
      (node (ref "VD14") (pin "K") (pinfunction "K_K") (pintype "passive"))
      (node (ref "VD15") (pin "K") (pinfunction "K_K") (pintype "passive"))
    )
    (net (code "60") (name "Net-(IC25-CSLEW)") (class "Default")
      (node (ref "C83") (pin "1") (pinfunction "1_1") (pintype "passive"))
      (node (ref "IC25") (pin "5") (pinfunction "CSLEW_5") (pintype "output"))
      (node (ref "R136") (pin "1") (pinfunction "1_1") (pintype "passive"))
      (node (ref "R138") (pin "2") (pinfunction "2_2") (pintype "passive"))
    )
    (net (code "61") (name "Net-(IC25-EN)") (class "Default")
      (node (ref "IC25") (pin "3") (pinfunction "EN_3") (pintype "input"))
      (node (ref "R134") (pin "1") (pinfunction "1_1") (pintype "passive"))
      (node (ref "R135") (pin "1") (pinfunction "1_1") (pintype "passive"))
      (node (ref "R137") (pin "1") (pinfunction "1_1") (pintype "passive"))
    )
    (net (code "62") (name "Net-(IC25-FAULT{slash})") (class "Default")
      (node (ref "IC25") (pin "4") (pinfunction "FAULT/_4") (pintype "output"))
      (node (ref "R139") (pin "1") (pinfunction "1_1") (pintype "passive"))
    )
    (net (code "63") (name "Net-(IC28-CSLEW)") (class "Default")
      (node (ref "C88") (pin "1") (pinfunction "1_1") (pintype "passive"))
      (node (ref "IC28") (pin "5") (pinfunction "CSLEW_5") (pintype "output"))
      (node (ref "R142") (pin "1") (pinfunction "1_1") (pintype "passive"))
      (node (ref "R144") (pin "2") (pinfunction "2_2") (pintype "passive"))
    )
    (net (code "64") (name "Net-(IC28-EN)") (class "Default")
      (node (ref "IC28") (pin "3") (pinfunction "EN_3") (pintype "input"))
      (node (ref "R141") (pin "1") (pinfunction "1_1") (pintype "passive"))
    )
    (net (code "65") (name "Net-(IC28-FAULT{slash})") (class "Default")
      (node (ref "IC28") (pin "4") (pinfunction "FAULT/_4") (pintype "output"))
      (node (ref "R143") (pin "2") (pinfunction "2_2") (pintype "passive"))
    )
    (net (code "66") (name "Net-(IC29-SSTX2+)") (class "Default")
      (node (ref "C93") (pin "1") (pinfunction "1_1") (pintype "passive"))
      (node (ref "IC29") (pin "13") (pinfunction "SSTX2+_13") (pintype "bidirectional"))
    )
    (net (code "67") (name "Net-(IC29-SSTX2-)") (class "Default")
      (node (ref "C91") (pin "1") (pinfunction "1_1") (pintype "passive"))
      (node (ref "IC29") (pin "14") (pinfunction "SSTX2-_14") (pintype "bidirectional"))
    )
    (net (code "68") (name "Net-(IC30-SSTX2+)") (class "Default")
      (node (ref "C94") (pin "1") (pinfunction "1_1") (pintype "passive"))
      (node (ref "IC30") (pin "13") (pinfunction "SSTX2+_13") (pintype "bidirectional"))
    )
    (net (code "69") (name "Net-(IC30-SSTX2-)") (class "Default")
      (node (ref "C92") (pin "1") (pinfunction "1_1") (pintype "passive"))
      (node (ref "IC30") (pin "14") (pinfunction "SSTX2-_14") (pintype "bidirectional"))
    )
    (net (code "70") (name "VCC3P3") (class "Default")
      (node (ref "C89") (pin "1") (pinfunction "1_1") (pintype "passive"))
      (node (ref "C90") (pin "1") (pinfunction "1_1") (pintype "passive"))
      (node (ref "C95") (pin "1") (pinfunction "1_1") (pintype "passive"))
      (node (ref "C96") (pin "1") (pinfunction "1_1") (pintype "passive"))
      (node (ref "IC26") (pin "9") (pinfunction "VCC_9") (pintype "power_in"))
      (node (ref "IC27") (pin "9") (pinfunction "VCC_9") (pintype "power_in"))
      (node (ref "IC29") (pin "17") (pinfunction "VDD_17") (pintype "power_in"))
      (node (ref "IC30") (pin "17") (pinfunction "VDD_17") (pintype "power_in"))
      (node (ref "R131") (pin "2") (pinfunction "2_2") (pintype "passive"))
    )
    (net (code "71") (name "VCC5P0") (class "Default")
      (node (ref "C80") (pin "1") (pinfunction "1_1") (pintype "passive"))
      (node (ref "C83") (pin "2") (pinfunction "2_2") (pintype "passive"))
      (node (ref "C84") (pin "1") (pinfunction "1_1") (pintype "passive"))
      (node (ref "C88") (pin "2") (pinfunction "2_2") (pintype "passive"))
      (node (ref "IC25") (pin "1") (pinfunction "VIN_1") (pintype "input"))
      (node (ref "IC28") (pin "1") (pinfunction "VIN_1") (pintype "input"))
      (node (ref "R133") (pin "2") (pinfunction "2_2") (pintype "passive"))
      (node (ref "R134") (pin "2") (pinfunction "2_2") (pintype "passive"))
      (node (ref "R140") (pin "2") (pinfunction "2_2") (pintype "passive"))
      (node (ref "R141") (pin "2") (pinfunction "2_2") (pintype "passive"))
      (node (ref "R143") (pin "1") (pinfunction "1_1") (pintype "passive"))
    )
    (net (code "72") (name "VCC5P0_HDMI") (class "Default")
      (node (ref "C85") (pin "1") (pinfunction "1_1") (pintype "passive"))
      (node (ref "C86") (pin "1") (pinfunction "1_1") (pintype "passive"))
      (node (ref "C87") (pin "1") (pinfunction "1_1") (pintype "passive"))
      (node (ref "IC28") (pin "6") (pinfunction "VOUT_6") (pintype "output"))
      (node (ref "J30") (pin "18") (pinfunction "+5V_POWER_18") (pintype "power_in"))
      (node (ref "J31") (pin "18") (pinfunction "+5V_POWER_18") (pintype "power_in"))
      (node (ref "R140") (pin "1") (pinfunction "1_1") (pintype "passive"))
      (node (ref "R142") (pin "2") (pinfunction "2_2") (pintype "passive"))
    )
    (net (code "73") (name "VCC5P0_USBS") (class "Default")
      (node (ref "C79") (pin "2") (pinfunction "2_2") (pintype "passive"))
      (node (ref "C81") (pin "1") (pinfunction "1_1") (pintype "passive"))
      (node (ref "C82") (pin "2") (pinfunction "2_2") (pintype "passive"))
      (node (ref "IC25") (pin "6") (pinfunction "VOUT_6") (pintype "output"))
      (node (ref "J29") (pin "1") (pinfunction "VBUS_1") (pintype "power_in"))
      (node (ref "J29") (pin "10") (pinfunction "VBUS_10") (pintype "power_in"))
      (node (ref "R133") (pin "1") (pinfunction "1_1") (pintype "passive"))
      (node (ref "R136") (pin "2") (pinfunction "2_2") (pintype "passive"))
    )
    (net (code "74") (name "unconnected-(IC29-SSRX1+-Pad10)") (class "Default")
      (node (ref "IC29") (pin "10") (pinfunction "SSRX1+_10") (pintype "bidirectional+no_connect"))
    )
    (net (code "75") (name "unconnected-(IC29-SSRX1--Pad11)") (class "Default")
      (node (ref "IC29") (pin "11") (pinfunction "SSRX1-_11") (pintype "bidirectional+no_connect"))
    )
    (net (code "76") (name "unconnected-(IC29-SSTX1+-Pad15)") (class "Default")
      (node (ref "IC29") (pin "15") (pinfunction "SSTX1+_15") (pintype "bidirectional+no_connect"))
    )
    (net (code "77") (name "unconnected-(IC29-SSTX1--Pad16)") (class "Default")
      (node (ref "IC29") (pin "16") (pinfunction "SSTX1-_16") (pintype "bidirectional+no_connect"))
    )
    (net (code "78") (name "unconnected-(IC30-SSRX1+-Pad10)") (class "Default")
      (node (ref "IC30") (pin "10") (pinfunction "SSRX1+_10") (pintype "bidirectional+no_connect"))
    )
    (net (code "79") (name "unconnected-(IC30-SSRX1--Pad11)") (class "Default")
      (node (ref "IC30") (pin "11") (pinfunction "SSRX1-_11") (pintype "bidirectional+no_connect"))
    )
    (net (code "80") (name "unconnected-(IC30-SSTX1+-Pad15)") (class "Default")
      (node (ref "IC30") (pin "15") (pinfunction "SSTX1+_15") (pintype "bidirectional+no_connect"))
    )
    (net (code "81") (name "unconnected-(IC30-SSTX1--Pad16)") (class "Default")
      (node (ref "IC30") (pin "16") (pinfunction "SSTX1-_16") (pintype "bidirectional+no_connect"))
    )
    (net (code "82") (name "unconnected-(J29-STDA_SSRX+-Pad6)") (class "Default")
      (node (ref "J29") (pin "6") (pinfunction "STDA_SSRX+_6") (pintype "bidirectional"))
    )
    (net (code "83") (name "unconnected-(J29-STDA_SSRX--Pad5)") (class "Default")
      (node (ref "J29") (pin "5") (pinfunction "STDA_SSRX-_5") (pintype "bidirectional"))
    )
    (net (code "84") (name "unconnected-(J29-STDA_SSTX+-Pad9)") (class "Default")
      (node (ref "J29") (pin "9") (pinfunction "STDA_SSTX+_9") (pintype "bidirectional"))
    )
    (net (code "85") (name "unconnected-(J29-STDA_SSTX--Pad8)") (class "Default")
      (node (ref "J29") (pin "8") (pinfunction "STDA_SSTX-_8") (pintype "bidirectional"))
    )
  )
)
